# USB_C_Converter.net
KiCad netlist of a schematic drawn in Altium Designer
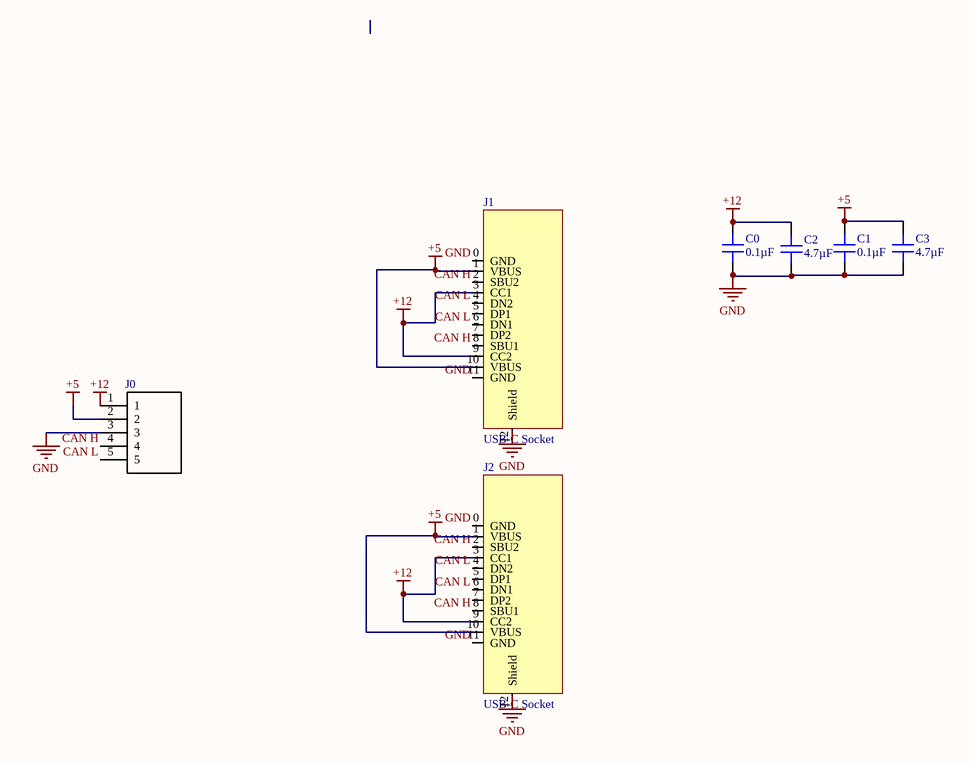
[diagram p0: USB_C_Converter.SchDoc]

(export (version "E")
  (design (tool "Eeschema 10.0.6"))
  (components
    (comp (ref "C0")
      (value "0.1µF")
      (footprint "CAP 0805_2012")
      (description "CAP CER 0.1UF 16V X7R 0805")
      (fields
        (field (name "PART NUMBER") "LLA219R71C104MA01L")
        (field (name "MANUFACTURER") "Murata Electronics")
      )
      (libsource (lib "Celestial Altium Library - altium_library") (part "Capacitor"))
    )
    (comp (ref "C1")
      (value "0.1µF")
      (footprint "CAP 0805_2012")
      (description "CAP CER 0.1UF 16V X7R 0805")
      (fields
        (field (name "PART NUMBER") "LLA219R71C104MA01L")
        (field (name "MANUFACTURER") "Murata Electronics")
      )
      (libsource (lib "Celestial Altium Library - altium_library") (part "Capacitor"))
    )
    (comp (ref "C2")
      (value "4.7µF")
      (footprint "CAP 0805_2012")
      (description "CAP CER 4.7UF 16V X7R 0805")
      (fields
        (field (name "PART NUMBER") "GRM21BR71C475KE51L")
        (field (name "MANUFACTURER") "Murata Electronics")
      )
      (libsource (lib "Celestial Altium Library - altium_library") (part "Capacitor"))
    )
    (comp (ref "C3")
      (value "4.7µF")
      (footprint "CAP 0805_2012")
      (description "CAP CER 4.7UF 16V X7R 0805")
      (fields
        (field (name "PART NUMBER") "GRM21BR71C475KE51L")
        (field (name "MANUFACTURER") "Murata Electronics")
      )
      (libsource (lib "Celestial Altium Library - altium_library") (part "Capacitor"))
    )
    (comp (ref "J0")
      (value "282834-5")
      (footprint "*TE_282834-5")
      (description "Buchanan; Conn; Term Blk; PCB; 5; 2.54mm; Front; 30-16 AWG; Green; 10 A; 150 V")
      (fields (field (name "MF") "TE Connectivity"))
      (libsource (lib "282834-5") (part "282834-5"))
    )
    (comp (ref "J1")
      (value "USB-C Socket")
      (footprint "TYPE-C-31-M-12")
      (libsource (lib "TYPE-C-31-M-12") (part "TYPE-C-31-M-12"))
    )
    (comp (ref "J2")
      (value "USB-C Socket")
      (footprint "TYPE-C-31-M-12")
      (libsource (lib "TYPE-C-31-M-12") (part "TYPE-C-31-M-12"))
    )
  )
  (nets
    (net (code "1") (name "+5") (class "Default")
      (node (ref "C1") (pin "2") (pinfunction "2_2") (pintype "passive"))
      (node (ref "C3") (pin "2") (pinfunction "2_2") (pintype "passive"))
      (node (ref "J0") (pin "2") (pinfunction "2_2") (pintype "passive"))
      (node (ref "J1") (pin "1") (pinfunction "VBUS_1") (pintype "passive"))
      (node (ref "J1") (pin "10") (pinfunction "VBUS_10") (pintype "passive"))
      (node (ref "J2") (pin "1") (pinfunction "VBUS_1") (pintype "passive"))
      (node (ref "J2") (pin "10") (pinfunction "VBUS_10") (pintype "passive"))
    )
    (net (code "2") (name "+12") (class "Default")
      (node (ref "C0") (pin "2") (pinfunction "2_2") (pintype "passive"))
      (node (ref "C2") (pin "2") (pinfunction "2_2") (pintype "passive"))
      (node (ref "J0") (pin "1") (pinfunction "1_1") (pintype "passive"))
      (node (ref "J1") (pin "3") (pinfunction "CC1_3") (pintype "passive"))
      (node (ref "J1") (pin "9") (pinfunction "CC2_9") (pintype "passive"))
      (node (ref "J2") (pin "3") (pinfunction "CC1_3") (pintype "passive"))
      (node (ref "J2") (pin "9") (pinfunction "CC2_9") (pintype "passive"))
    )
    (net (code "3") (name "/CAN H") (class "Default")
      (node (ref "J0") (pin "4") (pinfunction "4_4") (pintype "passive"))
      (node (ref "J1") (pin "2") (pinfunction "SBU2_2") (pintype "passive"))
      (node (ref "J1") (pin "8") (pinfunction "SBU1_8") (pintype "passive"))
      (node (ref "J2") (pin "2") (pinfunction "SBU2_2") (pintype "passive"))
      (node (ref "J2") (pin "8") (pinfunction "SBU1_8") (pintype "passive"))
    )
    (net (code "4") (name "/CAN L") (class "Default")
      (node (ref "J0") (pin "5") (pinfunction "5_5") (pintype "passive"))
      (node (ref "J1") (pin "4") (pinfunction "DN2_4") (pintype "passive"))
      (node (ref "J1") (pin "6") (pinfunction "DN1_6") (pintype "passive"))
      (node (ref "J2") (pin "4") (pinfunction "DN2_4") (pintype "passive"))
      (node (ref "J2") (pin "6") (pinfunction "DN1_6") (pintype "passive"))
    )
    (net (code "5") (name "GND") (class "Default")
      (node (ref "C0") (pin "1") (pinfunction "1_1") (pintype "passive"))
      (node (ref "C1") (pin "1") (pinfunction "1_1") (pintype "passive"))
      (node (ref "C2") (pin "1") (pinfunction "1_1") (pintype "passive"))
      (node (ref "C3") (pin "1") (pinfunction "1_1") (pintype "passive"))
      (node (ref "J0") (pin "3") (pinfunction "3_3") (pintype "passive"))
      (node (ref "J1") (pin "0") (pinfunction "GND_0") (pintype "passive"))
      (node (ref "J1") (pin "11") (pinfunction "GND_11") (pintype "passive"))
      (node (ref "J1") (pin "12") (pinfunction "Shield_12") (pintype "passive"))
      (node (ref "J2") (pin "0") (pinfunction "GND_0") (pintype "passive"))
      (node (ref "J2") (pin "11") (pinfunction "GND_11") (pintype "passive"))
      (node (ref "J2") (pin "12") (pinfunction "Shield_12") (pintype "passive"))
    )
    (net (code "6") (name "unconnected-(J1-DP1-Pad5)") (class "Default")
      (node (ref "J1") (pin "5") (pinfunction "DP1_5") (pintype "passive"))
    )
    (net (code "7") (name "unconnected-(J1-DP2-Pad7)") (class "Default")
      (node (ref "J1") (pin "7") (pinfunction "DP2_7") (pintype "passive"))
    )
    (net (code "8") (name "unconnected-(J2-DP1-Pad5)") (class "Default")
      (node (ref "J2") (pin "5") (pinfunction "DP1_5") (pintype "passive"))
    )
    (net (code "9") (name "unconnected-(J2-DP2-Pad7)") (class "Default")
      (node (ref "J2") (pin "7") (pinfunction "DP2_7") (pintype "passive"))
    )
  )
)
